# SCH_cmv4000.net
KiCad netlist of a schematic drawn in Altium Designer
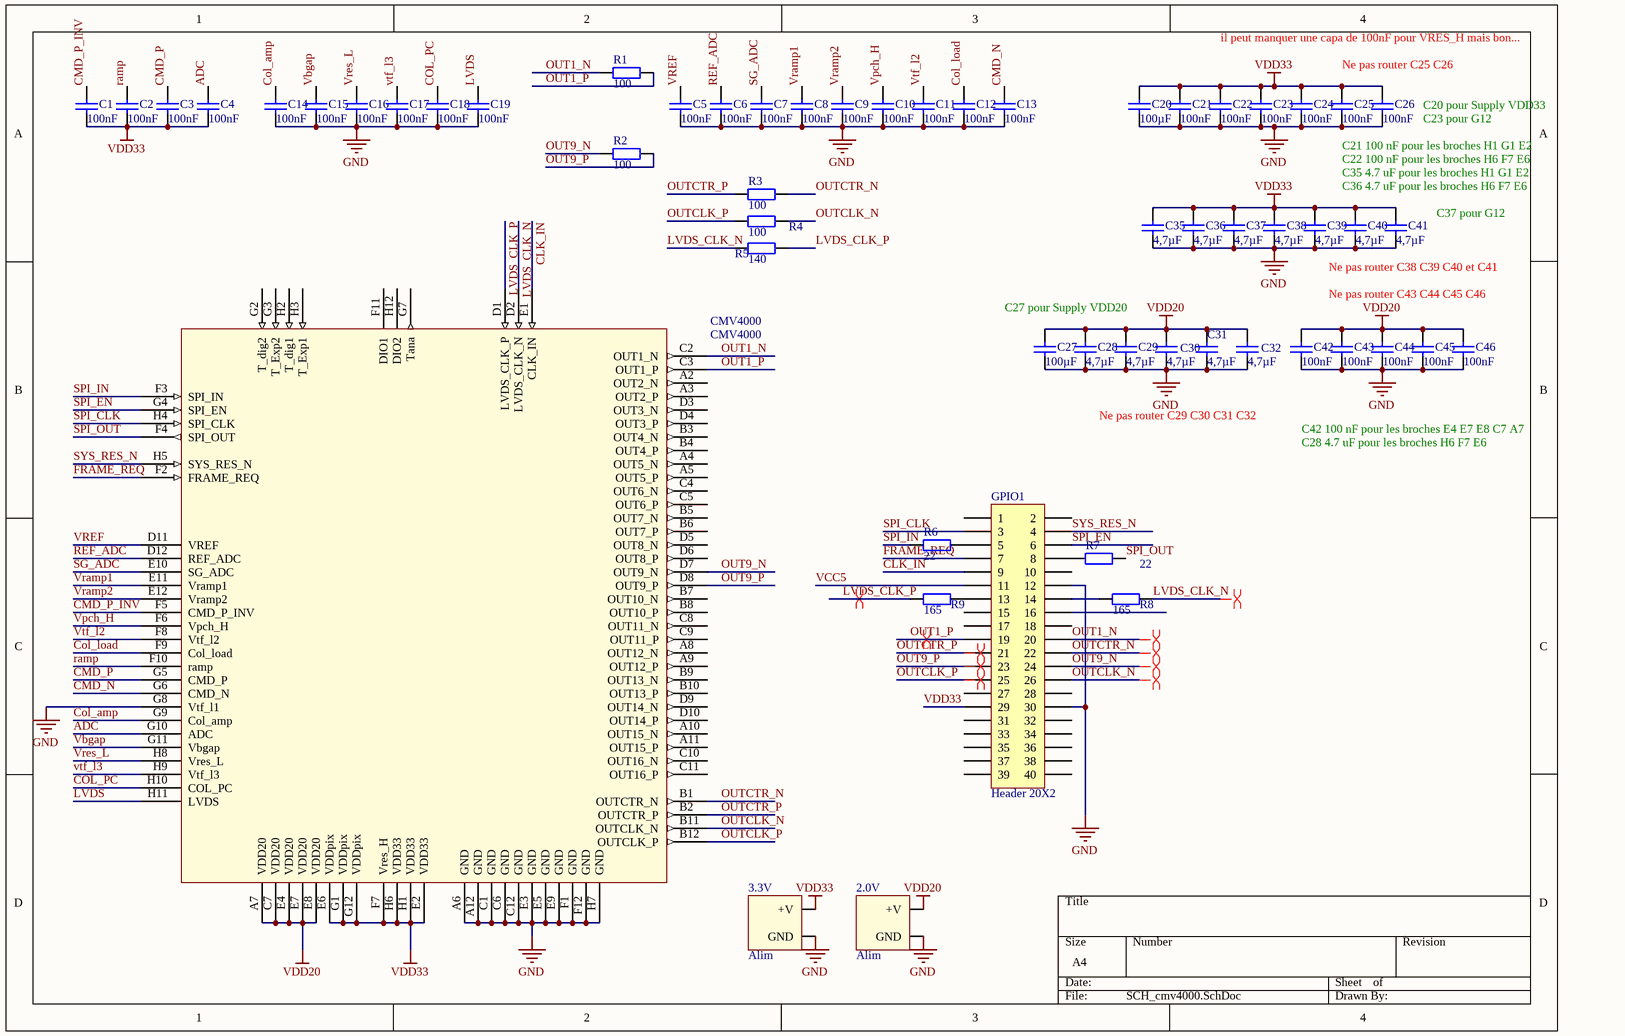
[diagram p0: SCH_cmv4000.SchDoc]

(export (version "E")
  (design (tool "Eeschema 10.0.6"))
  (components
    (comp (ref "2.0V")
      (value "Alim")
      (footprint "HDR1X2")
      (description "Connecteur d'alimentation")
      (fields
        (field (name "MANUFACTURER") "IMO PRECISION CONTROLS")
        (field (name "MANUFACTURER PART NUMBER") "21.95MH/2")
      )
      (libsource (lib "GEII1") (part "Connecteur Alimentation"))
    )
    (comp (ref "3.3V")
      (value "Alim")
      (footprint "HDR1X2")
      (description "Connecteur d'alimentation")
      (fields
        (field (name "MANUFACTURER") "IMO PRECISION CONTROLS")
        (field (name "MANUFACTURER PART NUMBER") "21.95MH/2")
      )
      (libsource (lib "GEII1") (part "Connecteur Alimentation"))
    )
    (comp (ref "C1")
      (value "100nF")
      (footprint "C1206")
      (description "Capacitor (Semiconductor SIM Model)")
      (fields (field (name "Comment") "Cap Semi") (field (name "PUBLISHER") "Altium Limited"))
      (libsource (lib "Miscellaneous Devices") (part "Cap Semi"))
    )
    (comp (ref "C2")
      (value "100nF")
      (footprint "C1206")
      (description "Capacitor (Semiconductor SIM Model)")
      (fields (field (name "Comment") "Cap Semi") (field (name "PUBLISHER") "Altium Limited"))
      (libsource (lib "Miscellaneous Devices") (part "Cap Semi"))
    )
    (comp (ref "C3")
      (value "100nF")
      (footprint "C1206")
      (description "Capacitor (Semiconductor SIM Model)")
      (fields (field (name "Comment") "Cap Semi") (field (name "PUBLISHER") "Altium Limited"))
      (libsource (lib "Miscellaneous Devices") (part "Cap Semi"))
    )
    (comp (ref "C4")
      (value "100nF")
      (footprint "C1206")
      (description "Capacitor (Semiconductor SIM Model)")
      (fields (field (name "Comment") "Cap Semi") (field (name "PUBLISHER") "Altium Limited"))
      (libsource (lib "Miscellaneous Devices") (part "Cap Semi"))
    )
    (comp (ref "C5")
      (value "100nF")
      (footprint "C1206")
      (description "Capacitor (Semiconductor SIM Model)")
      (fields (field (name "Comment") "Cap Semi") (field (name "PUBLISHER") "Altium Limited"))
      (libsource (lib "Miscellaneous Devices") (part "Cap Semi"))
    )
    (comp (ref "C6")
      (value "100nF")
      (footprint "C1206")
      (description "Capacitor (Semiconductor SIM Model)")
      (fields (field (name "Comment") "Cap Semi") (field (name "PUBLISHER") "Altium Limited"))
      (libsource (lib "Miscellaneous Devices") (part "Cap Semi"))
    )
    (comp (ref "C7")
      (value "100nF")
      (footprint "C1206")
      (description "Capacitor (Semiconductor SIM Model)")
      (fields (field (name "Comment") "Cap Semi") (field (name "PUBLISHER") "Altium Limited"))
      (libsource (lib "Miscellaneous Devices") (part "Cap Semi"))
    )
    (comp (ref "C8")
      (value "100nF")
      (footprint "C1206")
      (description "Capacitor (Semiconductor SIM Model)")
      (fields (field (name "Comment") "Cap Semi") (field (name "PUBLISHER") "Altium Limited"))
      (libsource (lib "Miscellaneous Devices") (part "Cap Semi"))
    )
    (comp (ref "C9")
      (value "100nF")
      (footprint "C1206")
      (description "Capacitor (Semiconductor SIM Model)")
      (fields (field (name "Comment") "Cap Semi") (field (name "PUBLISHER") "Altium Limited"))
      (libsource (lib "Miscellaneous Devices") (part "Cap Semi"))
    )
    (comp (ref "C10")
      (value "100nF")
      (footprint "C1206")
      (description "Capacitor (Semiconductor SIM Model)")
      (fields (field (name "Comment") "Cap Semi") (field (name "PUBLISHER") "Altium Limited"))
      (libsource (lib "Miscellaneous Devices") (part "Cap Semi"))
    )
    (comp (ref "C11")
      (value "100nF")
      (footprint "C1206")
      (description "Capacitor (Semiconductor SIM Model)")
      (fields (field (name "Comment") "Cap Semi") (field (name "PUBLISHER") "Altium Limited"))
      (libsource (lib "Miscellaneous Devices") (part "Cap Semi"))
    )
    (comp (ref "C12")
      (value "100nF")
      (footprint "C1206")
      (description "Capacitor (Semiconductor SIM Model)")
      (fields (field (name "Comment") "Cap Semi") (field (name "PUBLISHER") "Altium Limited"))
      (libsource (lib "Miscellaneous Devices") (part "Cap Semi"))
    )
    (comp (ref "C13")
      (value "100nF")
      (footprint "C1206")
      (description "Capacitor (Semiconductor SIM Model)")
      (fields (field (name "Comment") "Cap Semi") (field (name "PUBLISHER") "Altium Limited"))
      (libsource (lib "Miscellaneous Devices") (part "Cap Semi"))
    )
    (comp (ref "C14")
      (value "100nF")
      (footprint "C1206")
      (description "Capacitor (Semiconductor SIM Model)")
      (fields (field (name "Comment") "Cap Semi") (field (name "PUBLISHER") "Altium Limited"))
      (libsource (lib "Miscellaneous Devices") (part "Cap Semi"))
    )
    (comp (ref "C15")
      (value "100nF")
      (footprint "C1206")
      (description "Capacitor (Semiconductor SIM Model)")
      (fields (field (name "Comment") "Cap Semi") (field (name "PUBLISHER") "Altium Limited"))
      (libsource (lib "Miscellaneous Devices") (part "Cap Semi"))
    )
    (comp (ref "C16")
      (value "100nF")
      (footprint "C1206")
      (description "Capacitor (Semiconductor SIM Model)")
      (fields (field (name "Comment") "Cap Semi") (field (name "PUBLISHER") "Altium Limited"))
      (libsource (lib "Miscellaneous Devices") (part "Cap Semi"))
    )
    (comp (ref "C17")
      (value "100nF")
      (footprint "C1206")
      (description "Capacitor (Semiconductor SIM Model)")
      (fields (field (name "Comment") "Cap Semi") (field (name "PUBLISHER") "Altium Limited"))
      (libsource (lib "Miscellaneous Devices") (part "Cap Semi"))
    )
    (comp (ref "C18")
      (value "100nF")
      (footprint "C1206")
      (description "Capacitor (Semiconductor SIM Model)")
      (fields (field (name "Comment") "Cap Semi") (field (name "PUBLISHER") "Altium Limited"))
      (libsource (lib "Miscellaneous Devices") (part "Cap Semi"))
    )
    (comp (ref "C19")
      (value "100nF")
      (footprint "C1206")
      (description "Capacitor (Semiconductor SIM Model)")
      (fields (field (name "Comment") "Cap Semi") (field (name "PUBLISHER") "Altium Limited"))
      (libsource (lib "Miscellaneous Devices") (part "Cap Semi"))
    )
    (comp (ref "C20")
      (value "100µF")
      (footprint "C1206")
      (description "Capacitor (Semiconductor SIM Model)")
      (fields (field (name "Comment") "Cap Semi") (field (name "PUBLISHER") "Altium Limited"))
      (libsource (lib "Miscellaneous Devices") (part "Cap Semi"))
    )
    (comp (ref "C21")
      (value "100nF")
      (footprint "C1206")
      (description "Capacitor (Semiconductor SIM Model)")
      (fields (field (name "Comment") "Cap Semi") (field (name "PUBLISHER") "Altium Limited"))
      (libsource (lib "Miscellaneous Devices") (part "Cap Semi"))
    )
    (comp (ref "C22")
      (value "100nF")
      (footprint "C1206")
      (description "Capacitor (Semiconductor SIM Model)")
      (fields (field (name "Comment") "Cap Semi") (field (name "PUBLISHER") "Altium Limited"))
      (libsource (lib "Miscellaneous Devices") (part "Cap Semi"))
    )
    (comp (ref "C23")
      (value "100nF")
      (footprint "C1206")
      (description "Capacitor (Semiconductor SIM Model)")
      (fields (field (name "Comment") "Cap Semi") (field (name "PUBLISHER") "Altium Limited"))
      (libsource (lib "Miscellaneous Devices") (part "Cap Semi"))
    )
    (comp (ref "C24")
      (value "100nF")
      (footprint "C1206")
      (description "Capacitor (Semiconductor SIM Model)")
      (fields (field (name "Comment") "Cap Semi") (field (name "PUBLISHER") "Altium Limited"))
      (libsource (lib "Miscellaneous Devices") (part "Cap Semi"))
    )
    (comp (ref "C25")
      (value "100nF")
      (footprint "C1206")
      (description "Capacitor (Semiconductor SIM Model)")
      (fields (field (name "Comment") "Cap Semi") (field (name "PUBLISHER") "Altium Limited"))
      (libsource (lib "Miscellaneous Devices") (part "Cap Semi"))
    )
    (comp (ref "C26")
      (value "100nF")
      (footprint "C1206")
      (description "Capacitor (Semiconductor SIM Model)")
      (fields (field (name "Comment") "Cap Semi") (field (name "PUBLISHER") "Altium Limited"))
      (libsource (lib "Miscellaneous Devices") (part "Cap Semi"))
    )
    (comp (ref "C27")
      (value "100µF")
      (footprint "C1206")
      (description "Capacitor (Semiconductor SIM Model)")
      (fields (field (name "Comment") "Cap Semi") (field (name "PUBLISHER") "Altium Limited"))
      (libsource (lib "Miscellaneous Devices") (part "Cap Semi"))
    )
    (comp (ref "C28")
      (value "4,7µF")
      (footprint "C1206")
      (description "Capacitor (Semiconductor SIM Model)")
      (fields (field (name "Comment") "Cap Semi") (field (name "PUBLISHER") "Altium Limited"))
      (libsource (lib "Miscellaneous Devices") (part "Cap Semi"))
    )
    (comp (ref "C29")
      (value "4,7µF")
      (footprint "C1206")
      (description "Capacitor (Semiconductor SIM Model)")
      (fields (field (name "Comment") "Cap Semi") (field (name "PUBLISHER") "Altium Limited"))
      (libsource (lib "Miscellaneous Devices") (part "Cap Semi"))
    )
    (comp (ref "C30")
      (value "4,7µF")
      (footprint "C1206")
      (description "Capacitor (Semiconductor SIM Model)")
      (fields (field (name "Comment") "Cap Semi") (field (name "PUBLISHER") "Altium Limited"))
      (libsource (lib "Miscellaneous Devices") (part "Cap Semi"))
    )
    (comp (ref "C31")
      (value "4,7µF")
      (footprint "C1206")
      (description "Capacitor (Semiconductor SIM Model)")
      (fields (field (name "Comment") "Cap Semi") (field (name "PUBLISHER") "Altium Limited"))
      (libsource (lib "Miscellaneous Devices") (part "Cap Semi"))
    )
    (comp (ref "C32")
      (value "4,7µF")
      (footprint "C1206")
      (description "Capacitor (Semiconductor SIM Model)")
      (fields (field (name "Comment") "Cap Semi") (field (name "PUBLISHER") "Altium Limited"))
      (libsource (lib "Miscellaneous Devices") (part "Cap Semi"))
    )
    (comp (ref "C35")
      (value "4,7µF")
      (footprint "C1206")
      (description "Capacitor (Semiconductor SIM Model)")
      (fields (field (name "Comment") "Cap Semi") (field (name "PUBLISHER") "Altium Limited"))
      (libsource (lib "Miscellaneous Devices") (part "Cap Semi"))
    )
    (comp (ref "C36")
      (value "4,7µF")
      (footprint "C1206")
      (description "Capacitor (Semiconductor SIM Model)")
      (fields (field (name "Comment") "Cap Semi") (field (name "PUBLISHER") "Altium Limited"))
      (libsource (lib "Miscellaneous Devices") (part "Cap Semi"))
    )
    (comp (ref "C37")
      (value "4,7µF")
      (footprint "C1206")
      (description "Capacitor (Semiconductor SIM Model)")
      (fields (field (name "Comment") "Cap Semi") (field (name "PUBLISHER") "Altium Limited"))
      (libsource (lib "Miscellaneous Devices") (part "Cap Semi"))
    )
    (comp (ref "C38")
      (value "4,7µF")
      (footprint "C1206")
      (description "Capacitor (Semiconductor SIM Model)")
      (fields (field (name "Comment") "Cap Semi") (field (name "PUBLISHER") "Altium Limited"))
      (libsource (lib "Miscellaneous Devices") (part "Cap Semi"))
    )
    (comp (ref "C39")
      (value "4,7µF")
      (footprint "C1206")
      (description "Capacitor (Semiconductor SIM Model)")
      (fields (field (name "Comment") "Cap Semi") (field (name "PUBLISHER") "Altium Limited"))
      (libsource (lib "Miscellaneous Devices") (part "Cap Semi"))
    )
    (comp (ref "C40")
      (value "4,7µF")
      (footprint "C1206")
      (description "Capacitor (Semiconductor SIM Model)")
      (fields (field (name "Comment") "Cap Semi") (field (name "PUBLISHER") "Altium Limited"))
      (libsource (lib "Miscellaneous Devices") (part "Cap Semi"))
    )
    (comp (ref "C41")
      (value "4,7µF")
      (footprint "C1206")
      (description "Capacitor (Semiconductor SIM Model)")
      (fields (field (name "Comment") "Cap Semi") (field (name "PUBLISHER") "Altium Limited"))
      (libsource (lib "Miscellaneous Devices") (part "Cap Semi"))
    )
    (comp (ref "C42")
      (value "100nF")
      (footprint "C1206")
      (description "Capacitor (Semiconductor SIM Model)")
      (fields (field (name "Comment") "Cap Semi") (field (name "PUBLISHER") "Altium Limited"))
      (libsource (lib "Miscellaneous Devices") (part "Cap Semi"))
    )
    (comp (ref "C43")
      (value "100nF")
      (footprint "C1206")
      (description "Capacitor (Semiconductor SIM Model)")
      (fields (field (name "Comment") "Cap Semi") (field (name "PUBLISHER") "Altium Limited"))
      (libsource (lib "Miscellaneous Devices") (part "Cap Semi"))
    )
    (comp (ref "C44")
      (value "100nF")
      (footprint "C1206")
      (description "Capacitor (Semiconductor SIM Model)")
      (fields (field (name "Comment") "Cap Semi") (field (name "PUBLISHER") "Altium Limited"))
      (libsource (lib "Miscellaneous Devices") (part "Cap Semi"))
    )
    (comp (ref "C45")
      (value "100nF")
      (footprint "C1206")
      (description "Capacitor (Semiconductor SIM Model)")
      (fields (field (name "Comment") "Cap Semi") (field (name "PUBLISHER") "Altium Limited"))
      (libsource (lib "Miscellaneous Devices") (part "Cap Semi"))
    )
    (comp (ref "C46")
      (value "100nF")
      (footprint "C1206")
      (description "Capacitor (Semiconductor SIM Model)")
      (fields (field (name "Comment") "Cap Semi") (field (name "PUBLISHER") "Altium Limited"))
      (libsource (lib "Miscellaneous Devices") (part "Cap Semi"))
    )
    (comp (ref "CMV4000") (value "CMV4000") (footprint "PGA940") (libsource (lib "cmv4000") (part "CMV4000")))
    (comp (ref "GPIO1")
      (value "Header 20X2")
      (footprint "HDR2X20")
      (description "Header, 20-Pin, Dual row")
      (fields (field (name "PUBLISHER") "Altium Limited"))
      (libsource (lib "Miscellaneous Connectors") (part "Header 20X2"))
    )
    (comp (ref "R1")
      (value "100")
      (footprint "1206-R")
      (description "Resistance")
      (fields (field (name "PUBLISHER") "Altium Limited"))
      (libsource (lib "GEII1") (part "Res"))
    )
    (comp (ref "R2")
      (value "100")
      (footprint "1206-R")
      (description "Resistance")
      (fields (field (name "PUBLISHER") "Altium Limited"))
      (libsource (lib "GEII1") (part "Res"))
    )
    (comp (ref "R3")
      (value "100")
      (footprint "1206-R")
      (description "Resistance")
      (fields (field (name "PUBLISHER") "Altium Limited"))
      (libsource (lib "GEII1") (part "Res"))
    )
    (comp (ref "R4")
      (value "100")
      (footprint "1206-R")
      (description "Resistance")
      (fields (field (name "PUBLISHER") "Altium Limited"))
      (libsource (lib "GEII1") (part "Res"))
    )
    (comp (ref "R5")
      (value "140")
      (footprint "1206-R")
      (description "Resistance")
      (fields (field (name "PUBLISHER") "Altium Limited"))
      (libsource (lib "GEII1") (part "Res"))
    )
    (comp (ref "R6")
      (value "22")
      (footprint "1206-R")
      (description "Resistance")
      (fields (field (name "PUBLISHER") "Altium Limited"))
      (libsource (lib "GEII1") (part "Res"))
    )
    (comp (ref "R7")
      (value "22")
      (footprint "1206-R")
      (description "Resistance")
      (fields (field (name "PUBLISHER") "Altium Limited"))
      (libsource (lib "GEII1") (part "Res"))
    )
    (comp (ref "R8")
      (value "165")
      (footprint "1206-R")
      (description "Resistance")
      (fields (field (name "PUBLISHER") "Altium Limited"))
      (libsource (lib "GEII1") (part "Res"))
    )
    (comp (ref "R9")
      (value "165")
      (footprint "1206-R")
      (description "Resistance")
      (fields (field (name "PUBLISHER") "Altium Limited"))
      (libsource (lib "GEII1") (part "Res"))
    )
  )
  (nets
    (net (code "1") (name "/ADC") (class "Default")
      (node (ref "C4") (pin "2") (pinfunction "2_2") (pintype "passive"))
      (node (ref "CMV4000") (pin "G10") (pinfunction "ADC_G10") (pintype "passive"))
    )
    (net (code "2") (name "/CLK_IN") (class "Default")
      (node (ref "CMV4000") (pin "E1") (pinfunction "CLK_IN_E1") (pintype "input"))
      (node (ref "GPIO1") (pin "9") (pinfunction "9_9") (pintype "passive"))
    )
    (net (code "3") (name "/CMD_N") (class "Default")
      (node (ref "C13") (pin "2") (pinfunction "2_2") (pintype "passive"))
      (node (ref "CMV4000") (pin "G6") (pinfunction "CMD_N_G6") (pintype "passive"))
    )
    (net (code "4") (name "/CMD_P") (class "Default")
      (node (ref "C3") (pin "2") (pinfunction "2_2") (pintype "passive"))
      (node (ref "CMV4000") (pin "G5") (pinfunction "CMD_P_G5") (pintype "passive"))
    )
    (net (code "5") (name "/CMD_P_INV") (class "Default")
      (node (ref "C1") (pin "2") (pinfunction "2_2") (pintype "passive"))
      (node (ref "CMV4000") (pin "F5") (pinfunction "CMD_P_INV_F5") (pintype "passive"))
    )
    (net (code "6") (name "/COL_PC") (class "Default")
      (node (ref "C18") (pin "2") (pinfunction "2_2") (pintype "passive"))
      (node (ref "CMV4000") (pin "H10") (pinfunction "COL_PC_H10") (pintype "passive"))
    )
    (net (code "7") (name "/Col_amp") (class "Default")
      (node (ref "C14") (pin "2") (pinfunction "2_2") (pintype "passive"))
      (node (ref "CMV4000") (pin "G9") (pinfunction "Col_amp_G9") (pintype "passive"))
    )
    (net (code "8") (name "/Col_load") (class "Default")
      (node (ref "C12") (pin "2") (pinfunction "2_2") (pintype "passive"))
      (node (ref "CMV4000") (pin "F9") (pinfunction "Col_load_F9") (pintype "passive"))
    )
    (net (code "9") (name "/FRAME_REQ") (class "Default")
      (node (ref "CMV4000") (pin "F2") (pinfunction "FRAME_REQ_F2") (pintype "input"))
      (node (ref "GPIO1") (pin "7") (pinfunction "7_7") (pintype "passive"))
    )
    (net (code "10") (name "/LVDS") (class "Default")
      (node (ref "C19") (pin "2") (pinfunction "2_2") (pintype "passive"))
      (node (ref "CMV4000") (pin "H11") (pinfunction "LVDS_H11") (pintype "passive"))
    )
    (net (code "11") (name "/LVDS_CLK_N") (class "Default")
      (node (ref "CMV4000") (pin "D2") (pinfunction "LVDS_CLK_N_D2") (pintype "input"))
      (node (ref "R5") (pin "1") (pinfunction "1_1") (pintype "passive"))
      (node (ref "R8") (pin "2") (pinfunction "2_2") (pintype "passive"))
    )
    (net (code "12") (name "/LVDS_CLK_P") (class "Default")
      (node (ref "CMV4000") (pin "D1") (pinfunction "LVDS_CLK_P_D1") (pintype "input"))
      (node (ref "R5") (pin "2") (pinfunction "2_2") (pintype "passive"))
      (node (ref "R9") (pin "1") (pinfunction "1_1") (pintype "passive"))
    )
    (net (code "13") (name "/OUT1_N") (class "Default")
      (node (ref "CMV4000") (pin "C2") (pinfunction "OUT1_N_C2") (pintype "output"))
      (node (ref "GPIO1") (pin "20") (pinfunction "20_20") (pintype "passive"))
      (node (ref "R1") (pin "1") (pinfunction "1_1") (pintype "passive"))
    )
    (net (code "14") (name "/OUT1_P") (class "Default")
      (node (ref "CMV4000") (pin "C3") (pinfunction "OUT1_P_C3") (pintype "output"))
      (node (ref "GPIO1") (pin "19") (pinfunction "19_19") (pintype "passive"))
      (node (ref "R1") (pin "2") (pinfunction "2_2") (pintype "passive"))
    )
    (net (code "15") (name "/OUT9_N") (class "Default")
      (node (ref "CMV4000") (pin "D7") (pinfunction "OUT9_N_D7") (pintype "output"))
      (node (ref "GPIO1") (pin "24") (pinfunction "24_24") (pintype "passive"))
      (node (ref "R2") (pin "1") (pinfunction "1_1") (pintype "passive"))
    )
    (net (code "16") (name "/OUT9_P") (class "Default")
      (node (ref "CMV4000") (pin "D8") (pinfunction "OUT9_P_D8") (pintype "output"))
      (node (ref "GPIO1") (pin "23") (pinfunction "23_23") (pintype "passive"))
      (node (ref "R2") (pin "2") (pinfunction "2_2") (pintype "passive"))
    )
    (net (code "17") (name "/OUTCLK_N") (class "Default")
      (node (ref "CMV4000") (pin "B11") (pinfunction "OUTCLK_N_B11") (pintype "output"))
      (node (ref "GPIO1") (pin "26") (pinfunction "26_26") (pintype "passive"))
      (node (ref "R4") (pin "2") (pinfunction "2_2") (pintype "passive"))
    )
    (net (code "18") (name "/OUTCLK_P") (class "Default")
      (node (ref "CMV4000") (pin "B12") (pinfunction "OUTCLK_P_B12") (pintype "output"))
      (node (ref "GPIO1") (pin "25") (pinfunction "25_25") (pintype "passive"))
      (node (ref "R4") (pin "1") (pinfunction "1_1") (pintype "passive"))
    )
    (net (code "19") (name "/OUTCTR_N") (class "Default")
      (node (ref "CMV4000") (pin "B1") (pinfunction "OUTCTR_N_B1") (pintype "output"))
      (node (ref "GPIO1") (pin "22") (pinfunction "22_22") (pintype "passive"))
      (node (ref "R3") (pin "2") (pinfunction "2_2") (pintype "passive"))
    )
    (net (code "20") (name "/OUTCTR_P") (class "Default")
      (node (ref "CMV4000") (pin "B2") (pinfunction "OUTCTR_P_B2") (pintype "output"))
      (node (ref "GPIO1") (pin "21") (pinfunction "21_21") (pintype "passive"))
      (node (ref "R3") (pin "1") (pinfunction "1_1") (pintype "passive"))
    )
    (net (code "21") (name "/REF_ADC") (class "Default")
      (node (ref "C6") (pin "2") (pinfunction "2_2") (pintype "passive"))
      (node (ref "CMV4000") (pin "D12") (pinfunction "REF_ADC_D12") (pintype "passive"))
    )
    (net (code "22") (name "/SG_ADC") (class "Default")
      (node (ref "C7") (pin "2") (pinfunction "2_2") (pintype "passive"))
      (node (ref "CMV4000") (pin "E10") (pinfunction "SG_ADC_E10") (pintype "passive"))
    )
    (net (code "23") (name "/SPI_CLK") (class "Default")
      (node (ref "CMV4000") (pin "H4") (pinfunction "SPI_CLK_H4") (pintype "input"))
      (node (ref "GPIO1") (pin "3") (pinfunction "3_3") (pintype "passive"))
    )
    (net (code "24") (name "/SPI_EN") (class "Default")
      (node (ref "CMV4000") (pin "G4") (pinfunction "SPI_EN_G4") (pintype "input"))
      (node (ref "GPIO1") (pin "6") (pinfunction "6_6") (pintype "passive"))
    )
    (net (code "25") (name "/SPI_IN") (class "Default")
      (node (ref "CMV4000") (pin "F3") (pinfunction "SPI_IN_F3") (pintype "input"))
      (node (ref "R6") (pin "1") (pinfunction "1_1") (pintype "passive"))
    )
    (net (code "26") (name "/SPI_OUT") (class "Default")
      (node (ref "CMV4000") (pin "F4") (pinfunction "SPI_OUT_F4") (pintype "output"))
      (node (ref "R7") (pin "2") (pinfunction "2_2") (pintype "passive"))
    )
    (net (code "27") (name "/SYS_RES_N") (class "Default")
      (node (ref "CMV4000") (pin "H5") (pinfunction "SYS_RES_N_H5") (pintype "input"))
      (node (ref "GPIO1") (pin "4") (pinfunction "4_4") (pintype "passive"))
    )
    (net (code "28") (name "/VCC5") (class "Default")
      (node (ref "GPIO1") (pin "11") (pinfunction "11_11") (pintype "passive"))
    )
    (net (code "29") (name "/VREF") (class "Default")
      (node (ref "C5") (pin "2") (pinfunction "2_2") (pintype "passive"))
      (node (ref "CMV4000") (pin "D11") (pinfunction "VREF_D11") (pintype "passive"))
    )
    (net (code "30") (name "/Vbgap") (class "Default")
      (node (ref "C15") (pin "2") (pinfunction "2_2") (pintype "passive"))
      (node (ref "CMV4000") (pin "G11") (pinfunction "Vbgap_G11") (pintype "passive"))
    )
    (net (code "31") (name "/Vpch_H") (class "Default")
      (node (ref "C10") (pin "2") (pinfunction "2_2") (pintype "passive"))
      (node (ref "CMV4000") (pin "F6") (pinfunction "Vpch_H_F6") (pintype "passive"))
    )
    (net (code "32") (name "/Vramp1") (class "Default")
      (node (ref "C8") (pin "2") (pinfunction "2_2") (pintype "passive"))
      (node (ref "CMV4000") (pin "E11") (pinfunction "Vramp1_E11") (pintype "passive"))
    )
    (net (code "33") (name "/Vramp2") (class "Default")
      (node (ref "C9") (pin "2") (pinfunction "2_2") (pintype "passive"))
      (node (ref "CMV4000") (pin "E12") (pinfunction "Vramp2_E12") (pintype "passive"))
    )
    (net (code "34") (name "/Vres_L") (class "Default")
      (node (ref "C16") (pin "2") (pinfunction "2_2") (pintype "passive"))
      (node (ref "CMV4000") (pin "H8") (pinfunction "Vres_L_H8") (pintype "passive"))
    )
    (net (code "35") (name "/Vtf_l2") (class "Default")
      (node (ref "C11") (pin "2") (pinfunction "2_2") (pintype "passive"))
      (node (ref "CMV4000") (pin "F8") (pinfunction "Vtf_l2_F8") (pintype "passive"))
    )
    (net (code "36") (name "/ramp") (class "Default")
      (node (ref "C2") (pin "2") (pinfunction "2_2") (pintype "passive"))
      (node (ref "CMV4000") (pin "F10") (pinfunction "ramp_F10") (pintype "passive"))
    )
    (net (code "37") (name "/vtf_l3") (class "Default")
      (node (ref "C17") (pin "2") (pinfunction "2_2") (pintype "passive"))
      (node (ref "CMV4000") (pin "H9") (pinfunction "Vtf_l3_H9") (pintype "passive"))
    )
    (net (code "38") (name "GND") (class "Default")
      (node (ref "2.0V") (pin "1") (pinfunction "GND_1") (pintype "passive"))
      (node (ref "3.3V") (pin "1") (pinfunction "GND_1") (pintype "passive"))
      (node (ref "C10") (pin "1") (pinfunction "1_1") (pintype "passive"))
      (node (ref "C11") (pin "1") (pinfunction "1_1") (pintype "passive"))
      (node (ref "C12") (pin "1") (pinfunction "1_1") (pintype "passive"))
      (node (ref "C13") (pin "1") (pinfunction "1_1") (pintype "passive"))
      (node (ref "C14") (pin "1") (pinfunction "1_1") (pintype "passive"))
      (node (ref "C15") (pin "1") (pinfunction "1_1") (pintype "passive"))
      (node (ref "C16") (pin "1") (pinfunction "1_1") (pintype "passive"))
      (node (ref "C17") (pin "1") (pinfunction "1_1") (pintype "passive"))
      (node (ref "C18") (pin "1") (pinfunction "1_1") (pintype "passive"))
      (node (ref "C19") (pin "1") (pinfunction "1_1") (pintype "passive"))
      (node (ref "C20") (pin "1") (pinfunction "1_1") (pintype "passive"))
      (node (ref "C21") (pin "1") (pinfunction "1_1") (pintype "passive"))
      (node (ref "C22") (pin "1") (pinfunction "1_1") (pintype "passive"))
      (node (ref "C23") (pin "1") (pinfunction "1_1") (pintype "passive"))
      (node (ref "C24") (pin "1") (pinfunction "1_1") (pintype "passive"))
      (node (ref "C25") (pin "1") (pinfunction "1_1") (pintype "passive"))
      (node (ref "C26") (pin "1") (pinfunction "1_1") (pintype "passive"))
      (node (ref "C27") (pin "1") (pinfunction "1_1") (pintype "passive"))
      (node (ref "C28") (pin "1") (pinfunction "1_1") (pintype "passive"))
      (node (ref "C29") (pin "1") (pinfunction "1_1") (pintype "passive"))
      (node (ref "C30") (pin "1") (pinfunction "1_1") (pintype "passive"))
      (node (ref "C31") (pin "1") (pinfunction "1_1") (pintype "passive"))
      (node (ref "C32") (pin "1") (pinfunction "1_1") (pintype "passive"))
      (node (ref "C35") (pin "1") (pinfunction "1_1") (pintype "passive"))
      (node (ref "C36") (pin "1") (pinfunction "1_1") (pintype "passive"))
      (node (ref "C37") (pin "1") (pinfunction "1_1") (pintype "passive"))
      (node (ref "C38") (pin "1") (pinfunction "1_1") (pintype "passive"))
      (node (ref "C39") (pin "1") (pinfunction "1_1") (pintype "passive"))
      (node (ref "C40") (pin "1") (pinfunction "1_1") (pintype "passive"))
      (node (ref "C41") (pin "1") (pinfunction "1_1") (pintype "passive"))
      (node (ref "C42") (pin "1") (pinfunction "1_1") (pintype "passive"))
      (node (ref "C43") (pin "1") (pinfunction "1_1") (pintype "passive"))
      (node (ref "C44") (pin "1") (pinfunction "1_1") (pintype "passive"))
      (node (ref "C45") (pin "1") (pinfunction "1_1") (pintype "passive"))
      (node (ref "C46") (pin "1") (pinfunction "1_1") (pintype "passive"))
      (node (ref "C5") (pin "1") (pinfunction "1_1") (pintype "passive"))
      (node (ref "C6") (pin "1") (pinfunction "1_1") (pintype "passive"))
      (node (ref "C7") (pin "1") (pinfunction "1_1") (pintype "passive"))
      (node (ref "C8") (pin "1") (pinfunction "1_1") (pintype "passive"))
      (node (ref "C9") (pin "1") (pinfunction "1_1") (pintype "passive"))
      (node (ref "CMV4000") (pin "A12") (pinfunction "GND_A12") (pintype "power_in"))
      (node (ref "CMV4000") (pin "A6") (pinfunction "GND_A6") (pintype "power_in"))
      (node (ref "CMV4000") (pin "C1") (pinfunction "GND_C1") (pintype "power_in"))
      (node (ref "CMV4000") (pin "C12") (pinfunction "GND_C12") (pintype "power_in"))
      (node (ref "CMV4000") (pin "C6") (pinfunction "GND_C6") (pintype "power_in"))
      (node (ref "CMV4000") (pin "E3") (pinfunction "GND_E3") (pintype "power_in"))
      (node (ref "CMV4000") (pin "E5") (pinfunction "GND_E5") (pintype "power_in"))
      (node (ref "CMV4000") (pin "E9") (pinfunction "GND_E9") (pintype "power_in"))
      (node (ref "CMV4000") (pin "F1") (pinfunction "GND_F1") (pintype "passive"))
      (node (ref "CMV4000") (pin "F12") (pinfunction "GND_F12") (pintype "passive"))
      (node (ref "CMV4000") (pin "G8") (pinfunction "Vtf_l1_G8") (pintype "passive"))
      (node (ref "CMV4000") (pin "H7") (pinfunction "GND_H7") (pintype "passive"))
      (node (ref "GPIO1") (pin "12") (pinfunction "12_12") (pintype "passive"))
      (node (ref "GPIO1") (pin "30") (pinfunction "30_30") (pintype "passive"))
    )
    (net (code "39") (name "Net-(GPIO1-Pad5)") (class "Default")
      (node (ref "GPIO1") (pin "5") (pinfunction "5_5") (pintype "passive"))
      (node (ref "R6") (pin "2") (pinfunction "2_2") (pintype "passive"))
    )
    (net (code "40") (name "Net-(GPIO1-Pad8)") (class "Default")
      (node (ref "GPIO1") (pin "8") (pinfunction "8_8") (pintype "passive"))
      (node (ref "R7") (pin "1") (pinfunction "1_1") (pintype "passive"))
    )
    (net (code "41") (name "Net-(GPIO1-Pad13)") (class "Default")
      (node (ref "GPIO1") (pin "13") (pinfunction "13_13") (pintype "passive"))
      (node (ref "R9") (pin "2") (pinfunction "2_2") (pintype "passive"))
    )
    (net (code "42") (name "Net-(GPIO1-Pad14)") (class "Default")
      (node (ref "GPIO1") (pin "14") (pinfunction "14_14") (pintype "passive"))
      (node (ref "R8") (pin "1") (pinfunction "1_1") (pintype "passive"))
    )
    (net (code "43") (name "VDD20") (class "Default")
      (node (ref "2.0V") (pin "2") (pinfunction "+V_2") (pintype "passive"))
      (node (ref "C27") (pin "2") (pinfunction "2_2") (pintype "passive"))
      (node (ref "C28") (pin "2") (pinfunction "2_2") (pintype "passive"))
      (node (ref "C29") (pin "2") (pinfunction "2_2") (pintype "passive"))
      (node (ref "C30") (pin "2") (pinfunction "2_2") (pintype "passive"))
      (node (ref "C31") (pin "2") (pinfunction "2_2") (pintype "passive"))
      (node (ref "C32") (pin "2") (pinfunction "2_2") (pintype "passive"))
      (node (ref "C42") (pin "2") (pinfunction "2_2") (pintype "passive"))
      (node (ref "C43") (pin "2") (pinfunction "2_2") (pintype "passive"))
      (node (ref "C44") (pin "2") (pinfunction "2_2") (pintype "passive"))
      (node (ref "C45") (pin "2") (pinfunction "2_2") (pintype "passive"))
      (node (ref "C46") (pin "2") (pinfunction "2_2") (pintype "passive"))
      (node (ref "CMV4000") (pin "A7") (pinfunction "VDD20_A7") (pintype "power_in"))
      (node (ref "CMV4000") (pin "C7") (pinfunction "VDD20_C7") (pintype "power_in"))
      (node (ref "CMV4000") (pin "E4") (pinfunction "VDD20_E4") (pintype "power_in"))
      (node (ref "CMV4000") (pin "E7") (pinfunction "VDD20_E7") (pintype "power_in"))
      (node (ref "CMV4000") (pin "E8") (pinfunction "VDD20_E8") (pintype "power_in"))
    )
    (net (code "44") (name "VDD33") (class "Default")
      (node (ref "3.3V") (pin "2") (pinfunction "+V_2") (pintype "passive"))
      (node (ref "C1") (pin "1") (pinfunction "1_1") (pintype "passive"))
      (node (ref "C2") (pin "1") (pinfunction "1_1") (pintype "passive"))
      (node (ref "C20") (pin "2") (pinfunction "2_2") (pintype "passive"))
      (node (ref "C21") (pin "2") (pinfunction "2_2") (pintype "passive"))
      (node (ref "C22") (pin "2") (pinfunction "2_2") (pintype "passive"))
      (node (ref "C23") (pin "2") (pinfunction "2_2") (pintype "passive"))
      (node (ref "C24") (pin "2") (pinfunction "2_2") (pintype "passive"))
      (node (ref "C25") (pin "2") (pinfunction "2_2") (pintype "passive"))
      (node (ref "C26") (pin "2") (pinfunction "2_2") (pintype "passive"))
      (node (ref "C3") (pin "1") (pinfunction "1_1") (pintype "passive"))
      (node (ref "C35") (pin "2") (pinfunction "2_2") (pintype "passive"))
      (node (ref "C36") (pin "2") (pinfunction "2_2") (pintype "passive"))
      (node (ref "C37") (pin "2") (pinfunction "2_2") (pintype "passive"))
      (node (ref "C38") (pin "2") (pinfunction "2_2") (pintype "passive"))
      (node (ref "C39") (pin "2") (pinfunction "2_2") (pintype "passive"))
      (node (ref "C4") (pin "1") (pinfunction "1_1") (pintype "passive"))
      (node (ref "C40") (pin "2") (pinfunction "2_2") (pintype "passive"))
      (node (ref "C41") (pin "2") (pinfunction "2_2") (pintype "passive"))
      (node (ref "CMV4000") (pin "E2") (pinfunction "VDD33_E2") (pintype "power_in"))
      (node (ref "CMV4000") (pin "E6") (pinfunction "VDDpix_E6") (pintype "power_in"))
      (node (ref "CMV4000") (pin "F7") (pinfunction "Vres_H_F7") (pintype "passive"))
      (node (ref "CMV4000") (pin "G1") (pinfunction "VDDpix_G1") (pintype "passive"))
      (node (ref "CMV4000") (pin "G12") (pinfunction "VDDpix_G12") (pintype "passive"))
      (node (ref "CMV4000") (pin "H1") (pinfunction "VDD33_H1") (pintype "passive"))
      (node (ref "CMV4000") (pin "H6") (pinfunction "VDD33_H6") (pintype "passive"))
      (node (ref "GPIO1") (pin "29") (pinfunction "29_29") (pintype "passive"))
    )
    (net (code "45") (name "unconnected-(CMV4000-DIO1-PadF11)") (class "Default")
      (node (ref "CMV4000") (pin "F11") (pinfunction "DIO1_F11") (pintype "passive"))
    )
    (net (code "46") (name "unconnected-(CMV4000-DIO2-PadH12)") (class "Default")
      (node (ref "CMV4000") (pin "H12") (pinfunction "DIO2_H12") (pintype "passive"))
    )
    (net (code "47") (name "unconnected-(CMV4000-OUT2_N-PadA2)") (class "Default")
      (node (ref "CMV4000") (pin "A2") (pinfunction "OUT2_N_A2") (pintype "output"))
    )
    (net (code "48") (name "unconnected-(CMV4000-OUT2_P-PadA3)") (class "Default")
      (node (ref "CMV4000") (pin "A3") (pinfunction "OUT2_P_A3") (pintype "output"))
    )
    (net (code "49") (name "unconnected-(CMV4000-OUT3_N-PadD3)") (class "Default")
      (node (ref "CMV4000") (pin "D3") (pinfunction "OUT3_N_D3") (pintype "output"))
    )
    (net (code "50") (name "unconnected-(CMV4000-OUT3_P-PadD4)") (class "Default")
      (node (ref "CMV4000") (pin "D4") (pinfunction "OUT3_P_D4") (pintype "output"))
    )
    (net (code "51") (name "unconnected-(CMV4000-OUT4_N-PadB3)") (class "Default")
      (node (ref "CMV4000") (pin "B3") (pinfunction "OUT4_N_B3") (pintype "output"))
    )
    (net (code "52") (name "unconnected-(CMV4000-OUT4_P-PadB4)") (class "Default")
      (node (ref "CMV4000") (pin "B4") (pinfunction "OUT4_P_B4") (pintype "output"))
    )
    (net (code "53") (name "unconnected-(CMV4000-OUT5_N-PadA4)") (class "Default")
      (node (ref "CMV4000") (pin "A4") (pinfunction "OUT5_N_A4") (pintype "output"))
    )
    (net (code "54") (name "unconnected-(CMV4000-OUT5_P-PadA5)") (class "Default")
      (node (ref "CMV4000") (pin "A5") (pinfunction "OUT5_P_A5") (pintype "output"))
    )
    (net (code "55") (name "unconnected-(CMV4000-OUT6_N-PadC4)") (class "Default")
      (node (ref "CMV4000") (pin "C4") (pinfunction "OUT6_N_C4") (pintype "output"))
    )
    (net (code "56") (name "unconnected-(CMV4000-OUT6_P-PadC5)") (class "Default")
      (node (ref "CMV4000") (pin "C5") (pinfunction "OUT6_P_C5") (pintype "output"))
    )
    (net (code "57") (name "unconnected-(CMV4000-OUT7_N-PadB5)") (class "Default")
      (node (ref "CMV4000") (pin "B5") (pinfunction "OUT7_N_B5") (pintype "output"))
    )
    (net (code "58") (name "unconnected-(CMV4000-OUT7_P-PadB6)") (class "Default")
      (node (ref "CMV4000") (pin "B6") (pinfunction "OUT7_P_B6") (pintype "output"))
    )
    (net (code "59") (name "unconnected-(CMV4000-OUT8_N-PadD5)") (class "Default")
      (node (ref "CMV4000") (pin "D5") (pinfunction "OUT8_N_D5") (pintype "output"))
    )
    (net (code "60") (name "unconnected-(CMV4000-OUT8_P-PadD6)") (class "Default")
      (node (ref "CMV4000") (pin "D6") (pinfunction "OUT8_P_D6") (pintype "output"))
    )
    (net (code "61") (name "unconnected-(CMV4000-OUT10_N-PadB7)") (class "Default")
      (node (ref "CMV4000") (pin "B7") (pinfunction "OUT10_N_B7") (pintype "output"))
    )
    (net (code "62") (name "unconnected-(CMV4000-OUT10_P-PadB8)") (class "Default")
      (node (ref "CMV4000") (pin "B8") (pinfunction "OUT10_P_B8") (pintype "output"))
    )
    (net (code "63") (name "unconnected-(CMV4000-OUT11_N-PadC8)") (class "Default")
      (node (ref "CMV4000") (pin "C8") (pinfunction "OUT11_N_C8") (pintype "output"))
    )
    (net (code "64") (name "unconnected-(CMV4000-OUT11_P-PadC9)") (class "Default")
      (node (ref "CMV4000") (pin "C9") (pinfunction "OUT11_P_C9") (pintype "output"))
    )
    (net (code "65") (name "unconnected-(CMV4000-OUT12_N-PadA8)") (class "Default")
      (node (ref "CMV4000") (pin "A8") (pinfunction "OUT12_N_A8") (pintype "output"))
    )
    (net (code "66") (name "unconnected-(CMV4000-OUT12_P-PadA9)") (class "Default")
      (node (ref "CMV4000") (pin "A9") (pinfunction "OUT12_P_A9") (pintype "output"))
    )
    (net (code "67") (name "unconnected-(CMV4000-OUT13_N-PadB9)") (class "Default")
      (node (ref "CMV4000") (pin "B9") (pinfunction "OUT13_N_B9") (pintype "output"))
    )
    (net (code "68") (name "unconnected-(CMV4000-OUT13_P-PadB10)") (class "Default")
      (node (ref "CMV4000") (pin "B10") (pinfunction "OUT13_P_B10") (pintype "output"))
    )
    (net (code "69") (name "unconnected-(CMV4000-OUT14_N-PadD9)") (class "Default")
      (node (ref "CMV4000") (pin "D9") (pinfunction "OUT14_N_D9") (pintype "output"))
    )
    (net (code "70") (name "unconnected-(CMV4000-OUT14_P-PadD10)") (class "Default")
      (node (ref "CMV4000") (pin "D10") (pinfunction "OUT14_P_D10") (pintype "output"))
    )
    (net (code "71") (name "unconnected-(CMV4000-OUT15_N-PadA10)") (class "Default")
      (node (ref "CMV4000") (pin "A10") (pinfunction "OUT15_N_A10") (pintype "output"))
    )
    (net (code "72") (name "unconnected-(CMV4000-OUT15_P-PadA11)") (class "Default")
      (node (ref "CMV4000") (pin "A11") (pinfunction "OUT15_P_A11") (pintype "output"))
    )
    (net (code "73") (name "unconnected-(CMV4000-OUT16_N-PadC10)") (class "Default")
      (node (ref "CMV4000") (pin "C10") (pinfunction "OUT16_N_C10") (pintype "output"))
    )
    (net (code "74") (name "unconnected-(CMV4000-OUT16_P-PadC11)") (class "Default")
      (node (ref "CMV4000") (pin "C11") (pinfunction "OUT16_P_C11") (pintype "output"))
    )
    (net (code "75") (name "unconnected-(CMV4000-T_Exp1-PadH3)") (class "Default")
      (node (ref "CMV4000") (pin "H3") (pinfunction "T_Exp1_H3") (pintype "input"))
    )
    (net (code "76") (name "unconnected-(CMV4000-T_Exp2-PadG3)") (class "Default")
      (node (ref "CMV4000") (pin "G3") (pinfunction "T_Exp2_G3") (pintype "input"))
    )
    (net (code "77") (name "unconnected-(CMV4000-T_dig1-PadH2)") (class "Default")
      (node (ref "CMV4000") (pin "H2") (pinfunction "T_dig1_H2") (pintype "input"))
    )
    (net (code "78") (name "unconnected-(CMV4000-T_dig2-PadG2)") (class "Default")
      (node (ref "CMV4000") (pin "G2") (pinfunction "T_dig2_G2") (pintype "input"))
    )
    (net (code "79") (name "unconnected-(CMV4000-Tana-PadG7)") (class "Default")
      (node (ref "CMV4000") (pin "G7") (pinfunction "Tana_G7") (pintype "output"))
    )
    (net (code "80") (name "unconnected-(GPIO1-Pad1)") (class "Default")
      (node (ref "GPIO1") (pin "1") (pinfunction "1_1") (pintype "passive"))
    )
    (net (code "81") (name "unconnected-(GPIO1-Pad2)") (class "Default")
      (node (ref "GPIO1") (pin "2") (pinfunction "2_2") (pintype "passive"))
    )
    (net (code "82") (name "unconnected-(GPIO1-Pad10)") (class "Default")
      (node (ref "GPIO1") (pin "10") (pinfunction "10_10") (pintype "passive"))
    )
    (net (code "83") (name "unconnected-(GPIO1-Pad15)") (class "Default")
      (node (ref "GPIO1") (pin "15") (pinfunction "15_15") (pintype "passive"))
    )
    (net (code "84") (name "unconnected-(GPIO1-Pad16)") (class "Default")
      (node (ref "GPIO1") (pin "16") (pinfunction "16_16") (pintype "passive"))
    )
    (net (code "85") (name "unconnected-(GPIO1-Pad17)") (class "Default")
      (node (ref "GPIO1") (pin "17") (pinfunction "17_17") (pintype "passive"))
    )
    (net (code "86") (name "unconnected-(GPIO1-Pad18)") (class "Default")
      (node (ref "GPIO1") (pin "18") (pinfunction "18_18") (pintype "passive"))
    )
    (net (code "87") (name "unconnected-(GPIO1-Pad27)") (class "Default")
      (node (ref "GPIO1") (pin "27") (pinfunction "27_27") (pintype "passive"))
    )
    (net (code "88") (name "unconnected-(GPIO1-Pad28)") (class "Default")
      (node (ref "GPIO1") (pin "28") (pinfunction "28_28") (pintype "passive"))
    )
    (net (code "89") (name "unconnected-(GPIO1-Pad31)") (class "Default")
      (node (ref "GPIO1") (pin "31") (pinfunction "31_31") (pintype "passive"))
    )
    (net (code "90") (name "unconnected-(GPIO1-Pad32)") (class "Default")
      (node (ref "GPIO1") (pin "32") (pinfunction "32_32") (pintype "passive"))
    )
    (net (code "91") (name "unconnected-(GPIO1-Pad33)") (class "Default")
      (node (ref "GPIO1") (pin "33") (pinfunction "33_33") (pintype "passive"))
    )
    (net (code "92") (name "unconnected-(GPIO1-Pad34)") (class "Default")
      (node (ref "GPIO1") (pin "34") (pinfunction "34_34") (pintype "passive"))
    )
    (net (code "93") (name "unconnected-(GPIO1-Pad35)") (class "Default")
      (node (ref "GPIO1") (pin "35") (pinfunction "35_35") (pintype "passive"))
    )
    (net (code "94") (name "unconnected-(GPIO1-Pad36)") (class "Default")
      (node (ref "GPIO1") (pin "36") (pinfunction "36_36") (pintype "passive"))
    )
    (net (code "95") (name "unconnected-(GPIO1-Pad37)") (class "Default")
      (node (ref "GPIO1") (pin "37") (pinfunction "37_37") (pintype "passive"))
    )
    (net (code "96") (name "unconnected-(GPIO1-Pad38)") (class "Default")
      (node (ref "GPIO1") (pin "38") (pinfunction "38_38") (pintype "passive"))
    )
    (net (code "97") (name "unconnected-(GPIO1-Pad39)") (class "Default")
      (node (ref "GPIO1") (pin "39") (pinfunction "39_39") (pintype "passive"))
    )
    (net (code "98") (name "unconnected-(GPIO1-Pad40)") (class "Default")
      (node (ref "GPIO1") (pin "40") (pinfunction "40_40") (pintype "passive"))
    )
  )
)
